# Motordrivare.net
KiCad netlist of a schematic drawn in Altium Designer
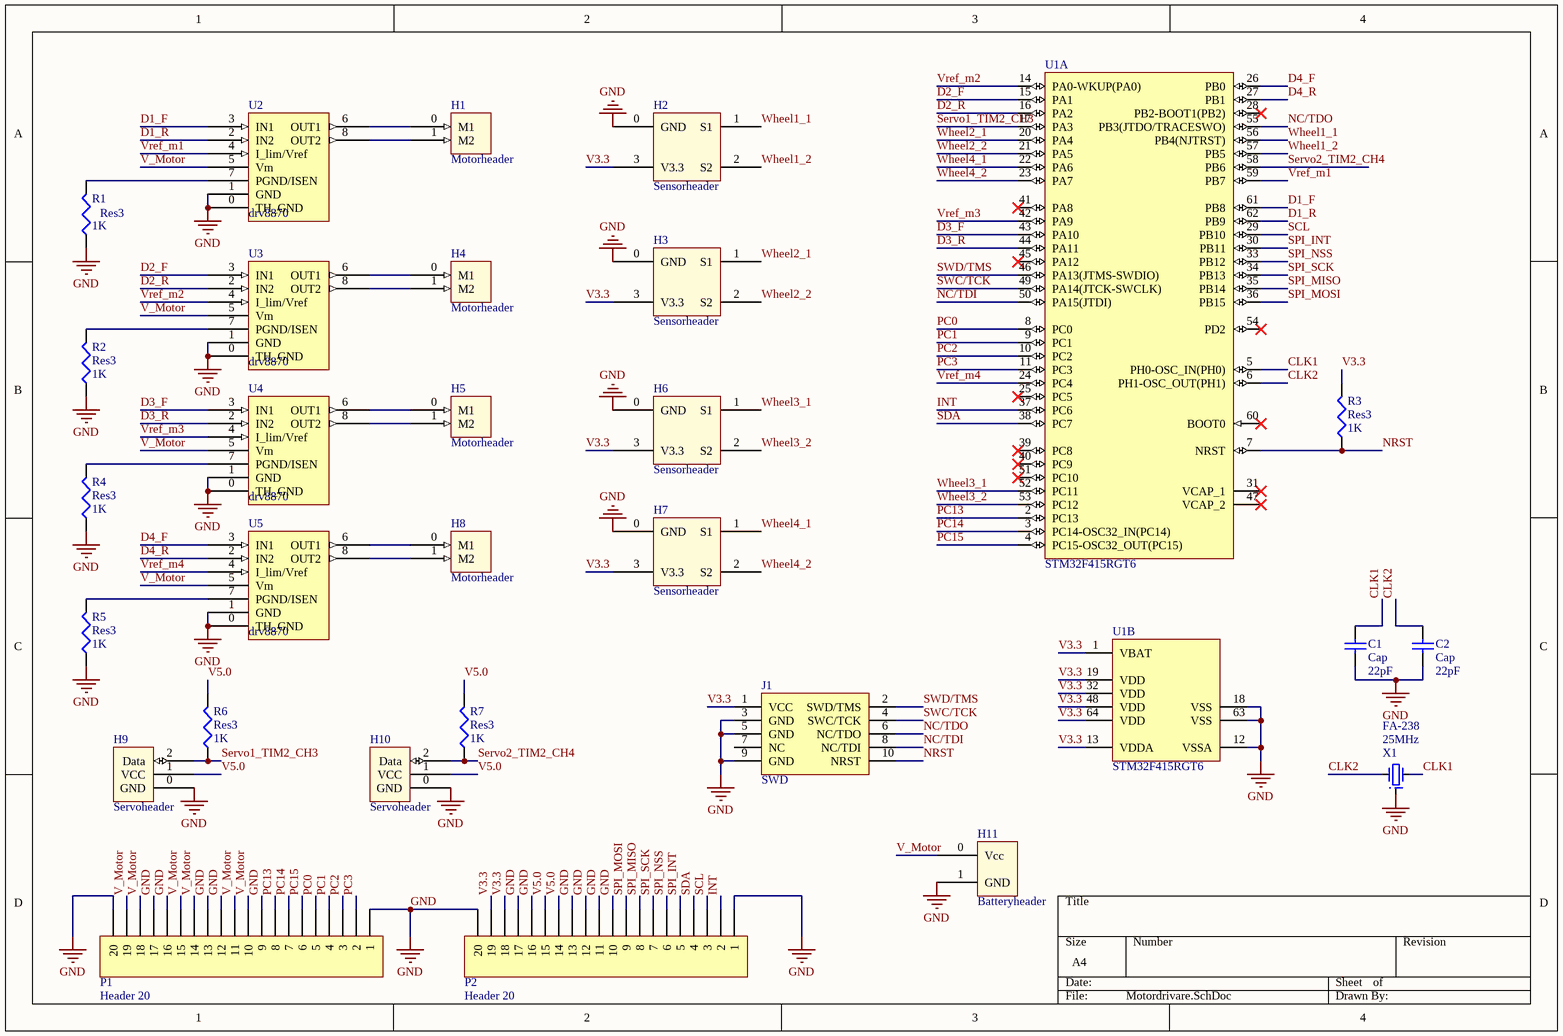
[diagram p0: Motordrivare.SchDoc]

(export (version "E")
  (design (tool "Eeschema 10.0.6"))
  (components
    (comp (ref "C1")
      (value "Cap")
      (footprint "6-0805_M")
      (description "Capacitor")
      (fields (field (name "ALTIUM_VALUE") "22pF") (field (name "PUBLISHER") "Altium Limited"))
      (libsource (lib "Miscellaneous Devices") (part "Cap"))
    )
    (comp (ref "C2")
      (value "Cap")
      (footprint "6-0805_M")
      (description "Capacitor")
      (fields (field (name "ALTIUM_VALUE") "22pF") (field (name "PUBLISHER") "Altium Limited"))
      (libsource (lib "Miscellaneous Devices") (part "Cap"))
    )
    (comp (ref "H1")
      (value "Motorheader")
      (footprint "Motorheader")
      (libsource (lib "Motorheader") (part "Motorheader"))
    )
    (comp (ref "H2")
      (value "Sensorheader")
      (footprint "Sensorheader")
      (libsource (lib "Sensorheader") (part "Sensorheader"))
    )
    (comp (ref "H3")
      (value "Sensorheader")
      (footprint "Sensorheader")
      (libsource (lib "Sensorheader") (part "Sensorheader"))
    )
    (comp (ref "H4")
      (value "Motorheader")
      (footprint "Motorheader")
      (libsource (lib "Motorheader") (part "Motorheader"))
    )
    (comp (ref "H5")
      (value "Motorheader")
      (footprint "Motorheader")
      (libsource (lib "Motorheader") (part "Motorheader"))
    )
    (comp (ref "H6")
      (value "Sensorheader")
      (footprint "Sensorheader")
      (libsource (lib "Sensorheader") (part "Sensorheader"))
    )
    (comp (ref "H7")
      (value "Sensorheader")
      (footprint "Sensorheader")
      (libsource (lib "Sensorheader") (part "Sensorheader"))
    )
    (comp (ref "H8")
      (value "Motorheader")
      (footprint "Motorheader")
      (libsource (lib "Motorheader") (part "Motorheader"))
    )
    (comp (ref "H9")
      (value "Servoheader")
      (footprint "Servoheader")
      (libsource (lib "Servoheader") (part "Servoheader"))
    )
    (comp (ref "H10")
      (value "Servoheader")
      (footprint "Servoheader")
      (libsource (lib "Servoheader") (part "Servoheader"))
    )
    (comp (ref "H11")
      (value "Batteryheader")
      (footprint "Batteryheader")
      (libsource (lib "Batteryheader") (part "Batteryheader"))
    )
    (comp (ref "J1")
      (value "SWD")
      (footprint "hdr_2x5_50mil")
      (description "SWD Header")
      (libsource (lib "lib_connectors") (part "hdr_swd"))
    )
    (comp (ref "P1")
      (value "Header 20")
      (footprint "HDR1X20")
      (description "Header, 20-Pin")
      (fields (field (name "PUBLISHER") "Altium Limited"))
      (libsource (lib "Miscellaneous Connectors") (part "Header 20"))
    )
    (comp (ref "P2")
      (value "Header 20")
      (footprint "HDR1X20")
      (description "Header, 20-Pin")
      (fields (field (name "PUBLISHER") "Altium Limited"))
      (libsource (lib "Miscellaneous Connectors") (part "Header 20"))
    )
    (comp (ref "R1")
      (value "Res3")
      (footprint "J1-0603")
      (description "Resistor")
      (fields (field (name "ALTIUM_VALUE") "1K") (field (name "PUBLISHER") "Altium Limited"))
      (libsource (lib "Miscellaneous Devices") (part "Res3"))
    )
    (comp (ref "R2")
      (value "Res3")
      (footprint "J1-0603")
      (description "Resistor")
      (fields (field (name "ALTIUM_VALUE") "1K") (field (name "PUBLISHER") "Altium Limited"))
      (libsource (lib "Miscellaneous Devices") (part "Res3"))
    )
    (comp (ref "R3")
      (value "Res3")
      (footprint "J1-0603")
      (description "Resistor")
      (fields (field (name "ALTIUM_VALUE") "1K") (field (name "PUBLISHER") "Altium Limited"))
      (libsource (lib "Miscellaneous Devices") (part "Res3"))
    )
    (comp (ref "R4")
      (value "Res3")
      (footprint "J1-0603")
      (description "Resistor")
      (fields (field (name "ALTIUM_VALUE") "1K") (field (name "PUBLISHER") "Altium Limited"))
      (libsource (lib "Miscellaneous Devices") (part "Res3"))
    )
    (comp (ref "R5")
      (value "Res3")
      (footprint "J1-0603")
      (description "Resistor")
      (fields (field (name "ALTIUM_VALUE") "1K") (field (name "PUBLISHER") "Altium Limited"))
      (libsource (lib "Miscellaneous Devices") (part "Res3"))
    )
    (comp (ref "R6")
      (value "Res3")
      (footprint "J1-0603")
      (description "Resistor")
      (fields (field (name "ALTIUM_VALUE") "1K") (field (name "PUBLISHER") "Altium Limited"))
      (libsource (lib "Miscellaneous Devices") (part "Res3"))
    )
    (comp (ref "R7")
      (value "Res3")
      (footprint "J1-0603")
      (description "Resistor")
      (fields (field (name "ALTIUM_VALUE") "1K") (field (name "PUBLISHER") "Altium Limited"))
      (libsource (lib "Miscellaneous Devices") (part "Res3"))
    )
    (comp (ref "U1")
      (value "STM32F415RGT6")
      (footprint "STM-LQFP64_N")
      (fields (field (name "MANUFACTURER") "STMicroelectronics"))
      (libsource (lib "lib_st") (part "STM32F415RGT6"))
    )
    (comp (ref "U2") (value "drv8870") (footprint "DRV8p") (libsource (lib "DRV8870") (part "drv8870")))
    (comp (ref "U3") (value "drv8870") (footprint "DRV8p") (libsource (lib "DRV8870") (part "drv8870")))
    (comp (ref "U4") (value "drv8870") (footprint "DRV8p") (libsource (lib "DRV8870") (part "drv8870")))
    (comp (ref "U5") (value "drv8870") (footprint "DRV8p") (libsource (lib "DRV8870") (part "drv8870")))
    (comp (ref "X1")
      (value "FA-238")
      (footprint "DFN220P320X70-4N")
      (description "Crystal With Shield")
      (fields (field (name "FREQ") "25MHz"))
      (libsource (lib "lib_passives") (part "crystal"))
    )
  )
  (nets
    (net (code "1") (name "/CLK1") (class "Default")
      (node (ref "C1") (pin "2") (pinfunction "2_2") (pintype "passive"))
      (node (ref "U1") (pin "5") (pinfunction "PH0-OSC_IN(PH0)_5") (pintype "bidirectional"))
      (node (ref "X1") (pin "2") (pinfunction "2_2") (pintype "passive"))
    )
    (net (code "2") (name "/CLK2") (class "Default")
      (node (ref "C2") (pin "2") (pinfunction "2_2") (pintype "passive"))
      (node (ref "U1") (pin "6") (pinfunction "PH1-OSC_OUT(PH1)_6") (pintype "bidirectional"))
      (node (ref "X1") (pin "1") (pinfunction "1_1") (pintype "passive"))
    )
    (net (code "3") (name "/D1_F") (class "Default")
      (node (ref "U1") (pin "61") (pinfunction "PB8_61") (pintype "bidirectional"))
      (node (ref "U2") (pin "3") (pinfunction "IN1_3") (pintype "input"))
    )
    (net (code "4") (name "/D1_R") (class "Default")
      (node (ref "U1") (pin "62") (pinfunction "PB9_62") (pintype "bidirectional"))
      (node (ref "U2") (pin "2") (pinfunction "IN2_2") (pintype "input"))
    )
    (net (code "5") (name "/D2_F") (class "Default")
      (node (ref "U1") (pin "15") (pinfunction "PA1_15") (pintype "bidirectional"))
      (node (ref "U3") (pin "3") (pinfunction "IN1_3") (pintype "input"))
    )
    (net (code "6") (name "/D2_R") (class "Default")
      (node (ref "U1") (pin "16") (pinfunction "PA2_16") (pintype "bidirectional"))
      (node (ref "U3") (pin "2") (pinfunction "IN2_2") (pintype "input"))
    )
    (net (code "7") (name "/D3_F") (class "Default")
      (node (ref "U1") (pin "43") (pinfunction "PA10_43") (pintype "bidirectional"))
      (node (ref "U4") (pin "3") (pinfunction "IN1_3") (pintype "input"))
    )
    (net (code "8") (name "/D3_R") (class "Default")
      (node (ref "U1") (pin "44") (pinfunction "PA11_44") (pintype "bidirectional"))
      (node (ref "U4") (pin "2") (pinfunction "IN2_2") (pintype "input"))
    )
    (net (code "9") (name "/D4_F") (class "Default")
      (node (ref "U1") (pin "26") (pinfunction "PB0_26") (pintype "bidirectional"))
      (node (ref "U5") (pin "3") (pinfunction "IN1_3") (pintype "input"))
    )
    (net (code "10") (name "/D4_R") (class "Default")
      (node (ref "U1") (pin "27") (pinfunction "PB1_27") (pintype "bidirectional"))
      (node (ref "U5") (pin "2") (pinfunction "IN2_2") (pintype "input"))
    )
    (net (code "11") (name "/INT") (class "Default")
      (node (ref "P2") (pin "2") (pinfunction "2_2") (pintype "passive"))
      (node (ref "U1") (pin "37") (pinfunction "PC6_37") (pintype "bidirectional"))
    )
    (net (code "12") (name "/NC{slash}TDI") (class "Default")
      (node (ref "J1") (pin "8") (pinfunction "NC/TDI_8") (pintype "passive"))
      (node (ref "U1") (pin "50") (pinfunction "PA15(JTDI)_50") (pintype "bidirectional"))
    )
    (net (code "13") (name "/NC{slash}TDO") (class "Default")
      (node (ref "J1") (pin "6") (pinfunction "NC/TDO_6") (pintype "passive"))
      (node (ref "U1") (pin "55") (pinfunction "PB3(JTDO/TRACESWO)_55") (pintype "bidirectional"))
    )
    (net (code "14") (name "/NRST") (class "Default")
      (node (ref "J1") (pin "10") (pinfunction "NRST_10") (pintype "passive"))
      (node (ref "R3") (pin "1") (pinfunction "1_1") (pintype "passive"))
      (node (ref "U1") (pin "7") (pinfunction "NRST_7") (pintype "bidirectional"))
    )
    (net (code "15") (name "/PC0") (class "Default")
      (node (ref "P1") (pin "5") (pinfunction "5_5") (pintype "passive"))
      (node (ref "U1") (pin "8") (pinfunction "PC0_8") (pintype "bidirectional"))
    )
    (net (code "16") (name "/PC1") (class "Default")
      (node (ref "P1") (pin "4") (pinfunction "4_4") (pintype "passive"))
      (node (ref "U1") (pin "9") (pinfunction "PC1_9") (pintype "bidirectional"))
    )
    (net (code "17") (name "/PC2") (class "Default")
      (node (ref "P1") (pin "3") (pinfunction "3_3") (pintype "passive"))
      (node (ref "U1") (pin "10") (pinfunction "PC2_10") (pintype "bidirectional"))
    )
    (net (code "18") (name "/PC3") (class "Default")
      (node (ref "P1") (pin "2") (pinfunction "2_2") (pintype "passive"))
      (node (ref "U1") (pin "11") (pinfunction "PC3_11") (pintype "bidirectional"))
    )
    (net (code "19") (name "/PC13") (class "Default")
      (node (ref "P1") (pin "8") (pinfunction "8_8") (pintype "passive"))
      (node (ref "U1") (pin "2") (pinfunction "PC13_2") (pintype "bidirectional"))
    )
    (net (code "20") (name "/PC14") (class "Default")
      (node (ref "P1") (pin "7") (pinfunction "7_7") (pintype "passive"))
      (node (ref "U1") (pin "3") (pinfunction "PC14-OSC32_IN(PC14)_3") (pintype "bidirectional"))
    )
    (net (code "21") (name "/PC15") (class "Default")
      (node (ref "P1") (pin "6") (pinfunction "6_6") (pintype "passive"))
      (node (ref "U1") (pin "4") (pinfunction "PC15-OSC32_OUT(PC15)_4") (pintype "bidirectional"))
    )
    (net (code "22") (name "/SCL") (class "Default")
      (node (ref "P2") (pin "3") (pinfunction "3_3") (pintype "passive"))
      (node (ref "U1") (pin "29") (pinfunction "PB10_29") (pintype "bidirectional"))
    )
    (net (code "23") (name "/SDA") (class "Default")
      (node (ref "P2") (pin "4") (pinfunction "4_4") (pintype "passive"))
      (node (ref "U1") (pin "38") (pinfunction "PC7_38") (pintype "bidirectional"))
    )
    (net (code "24") (name "/SPI_INT") (class "Default")
      (node (ref "P2") (pin "5") (pinfunction "5_5") (pintype "passive"))
      (node (ref "U1") (pin "30") (pinfunction "PB11_30") (pintype "bidirectional"))
    )
    (net (code "25") (name "/SPI_MISO") (class "Default")
      (node (ref "P2") (pin "8") (pinfunction "8_8") (pintype "passive"))
      (node (ref "U1") (pin "35") (pinfunction "PB14_35") (pintype "bidirectional"))
    )
    (net (code "26") (name "/SPI_MOSI") (class "Default")
      (node (ref "P2") (pin "9") (pinfunction "9_9") (pintype "passive"))
      (node (ref "U1") (pin "36") (pinfunction "PB15_36") (pintype "bidirectional"))
    )
    (net (code "27") (name "/SPI_NSS") (class "Default")
      (node (ref "P2") (pin "6") (pinfunction "6_6") (pintype "passive"))
      (node (ref "U1") (pin "33") (pinfunction "PB12_33") (pintype "bidirectional"))
    )
    (net (code "28") (name "/SPI_SCK") (class "Default")
      (node (ref "P2") (pin "7") (pinfunction "7_7") (pintype "passive"))
      (node (ref "U1") (pin "34") (pinfunction "PB13_34") (pintype "bidirectional"))
    )
    (net (code "29") (name "/SWC{slash}TCK") (class "Default")
      (node (ref "J1") (pin "4") (pinfunction "SWC/TCK_4") (pintype "passive"))
      (node (ref "U1") (pin "49") (pinfunction "PA14(JTCK-SWCLK)_49") (pintype "bidirectional"))
    )
    (net (code "30") (name "/SWD{slash}TMS") (class "Default")
      (node (ref "J1") (pin "2") (pinfunction "SWD/TMS_2") (pintype "passive"))
      (node (ref "U1") (pin "46") (pinfunction "PA13(JTMS-SWDIO)_46") (pintype "bidirectional"))
    )
    (net (code "31") (name "/Servo1_TIM2_CH3") (class "Default")
      (node (ref "H9") (pin "2") (pinfunction "Data_2") (pintype "bidirectional"))
      (node (ref "R6") (pin "1") (pinfunction "1_1") (pintype "passive"))
      (node (ref "U1") (pin "17") (pinfunction "PA3_17") (pintype "bidirectional"))
    )
    (net (code "32") (name "/Servo2_TIM2_CH4") (class "Default")
      (node (ref "H10") (pin "2") (pinfunction "Data_2") (pintype "bidirectional"))
      (node (ref "R7") (pin "1") (pinfunction "1_1") (pintype "passive"))
      (node (ref "U1") (pin "58") (pinfunction "PB6_58") (pintype "bidirectional"))
    )
    (net (code "33") (name "/V3.3") (class "Default")
      (node (ref "H2") (pin "3") (pinfunction "V3.3_3") (pintype "passive"))
      (node (ref "H3") (pin "3") (pinfunction "V3.3_3") (pintype "passive"))
      (node (ref "H6") (pin "3") (pinfunction "V3.3_3") (pintype "passive"))
      (node (ref "H7") (pin "3") (pinfunction "V3.3_3") (pintype "passive"))
      (node (ref "J1") (pin "1") (pinfunction "VCC_1") (pintype "passive"))
      (node (ref "P2") (pin "18") (pinfunction "18_18") (pintype "passive"))
      (node (ref "P2") (pin "19") (pinfunction "19_19") (pintype "passive"))
      (node (ref "R3") (pin "2") (pinfunction "2_2") (pintype "passive"))
      (node (ref "U1") (pin "1") (pinfunction "VBAT_1") (pintype "power_in"))
      (node (ref "U1") (pin "13") (pinfunction "VDDA_13") (pintype "power_in"))
      (node (ref "U1") (pin "19") (pinfunction "VDD_19") (pintype "power_in"))
      (node (ref "U1") (pin "32") (pinfunction "VDD_32") (pintype "power_in"))
      (node (ref "U1") (pin "48") (pinfunction "VDD_48") (pintype "power_in"))
      (node (ref "U1") (pin "64") (pinfunction "VDD_64") (pintype "power_in"))
    )
    (net (code "34") (name "/V5.0") (class "Default")
      (node (ref "H10") (pin "1") (pinfunction "VCC_1") (pintype "power_in"))
      (node (ref "H9") (pin "1") (pinfunction "VCC_1") (pintype "power_in"))
      (node (ref "P2") (pin "14") (pinfunction "14_14") (pintype "passive"))
      (node (ref "P2") (pin "15") (pinfunction "15_15") (pintype "passive"))
      (node (ref "R6") (pin "2") (pinfunction "2_2") (pintype "passive"))
      (node (ref "R7") (pin "2") (pinfunction "2_2") (pintype "passive"))
    )
    (net (code "35") (name "/V_Motor") (class "Default")
      (node (ref "H11") (pin "0") (pinfunction "Vcc_0") (pintype "power_in"))
      (node (ref "P1") (pin "10") (pinfunction "10_10") (pintype "passive"))
      (node (ref "P1") (pin "11") (pinfunction "11_11") (pintype "passive"))
      (node (ref "P1") (pin "14") (pinfunction "14_14") (pintype "passive"))
      (node (ref "P1") (pin "15") (pinfunction "15_15") (pintype "passive"))
      (node (ref "P1") (pin "18") (pinfunction "18_18") (pintype "passive"))
      (node (ref "P1") (pin "19") (pinfunction "19_19") (pintype "passive"))
      (node (ref "U2") (pin "5") (pinfunction "Vm_5") (pintype "power_in"))
      (node (ref "U3") (pin "5") (pinfunction "Vm_5") (pintype "power_in"))
      (node (ref "U4") (pin "5") (pinfunction "Vm_5") (pintype "power_in"))
      (node (ref "U5") (pin "5") (pinfunction "Vm_5") (pintype "power_in"))
    )
    (net (code "36") (name "/Vref_m1") (class "Default")
      (node (ref "U1") (pin "59") (pinfunction "PB7_59") (pintype "bidirectional"))
      (node (ref "U2") (pin "4") (pinfunction "I_lim/Vref_4") (pintype "input"))
    )
    (net (code "37") (name "/Vref_m2") (class "Default")
      (node (ref "U1") (pin "14") (pinfunction "PA0-WKUP(PA0)_14") (pintype "bidirectional"))
      (node (ref "U3") (pin "4") (pinfunction "I_lim/Vref_4") (pintype "input"))
    )
    (net (code "38") (name "/Vref_m3") (class "Default")
      (node (ref "U1") (pin "42") (pinfunction "PA9_42") (pintype "bidirectional"))
      (node (ref "U4") (pin "4") (pinfunction "I_lim/Vref_4") (pintype "input"))
    )
    (net (code "39") (name "/Vref_m4") (class "Default")
      (node (ref "U1") (pin "24") (pinfunction "PC4_24") (pintype "bidirectional"))
      (node (ref "U5") (pin "4") (pinfunction "I_lim/Vref_4") (pintype "input"))
    )
    (net (code "40") (name "/Wheel1_1") (class "Default")
      (node (ref "H2") (pin "1") (pinfunction "S1_1") (pintype "passive"))
      (node (ref "U1") (pin "56") (pinfunction "PB4(NJTRST)_56") (pintype "bidirectional"))
    )
    (net (code "41") (name "/Wheel1_2") (class "Default")
      (node (ref "H2") (pin "2") (pinfunction "S2_2") (pintype "passive"))
      (node (ref "U1") (pin "57") (pinfunction "PB5_57") (pintype "bidirectional"))
    )
    (net (code "42") (name "/Wheel2_1") (class "Default")
      (node (ref "H3") (pin "1") (pinfunction "S1_1") (pintype "passive"))
      (node (ref "U1") (pin "20") (pinfunction "PA4_20") (pintype "bidirectional"))
    )
    (net (code "43") (name "/Wheel2_2") (class "Default")
      (node (ref "H3") (pin "2") (pinfunction "S2_2") (pintype "passive"))
      (node (ref "U1") (pin "21") (pinfunction "PA5_21") (pintype "bidirectional"))
    )
    (net (code "44") (name "/Wheel3_1") (class "Default")
      (node (ref "H6") (pin "1") (pinfunction "S1_1") (pintype "passive"))
      (node (ref "U1") (pin "52") (pinfunction "PC11_52") (pintype "bidirectional"))
    )
    (net (code "45") (name "/Wheel3_2") (class "Default")
      (node (ref "H6") (pin "2") (pinfunction "S2_2") (pintype "passive"))
      (node (ref "U1") (pin "53") (pinfunction "PC12_53") (pintype "bidirectional"))
    )
    (net (code "46") (name "/Wheel4_1") (class "Default")
      (node (ref "H7") (pin "1") (pinfunction "S1_1") (pintype "passive"))
      (node (ref "U1") (pin "22") (pinfunction "PA6_22") (pintype "bidirectional"))
    )
    (net (code "47") (name "/Wheel4_2") (class "Default")
      (node (ref "H7") (pin "2") (pinfunction "S2_2") (pintype "passive"))
      (node (ref "U1") (pin "23") (pinfunction "PA7_23") (pintype "bidirectional"))
    )
    (net (code "48") (name "GND") (class "Default")
      (node (ref "C1") (pin "1") (pinfunction "1_1") (pintype "passive"))
      (node (ref "C2") (pin "1") (pinfunction "1_1") (pintype "passive"))
      (node (ref "H10") (pin "0") (pinfunction "GND_0") (pintype "power_in"))
      (node (ref "H11") (pin "1") (pinfunction "GND_1") (pintype "power_in"))
      (node (ref "H2") (pin "0") (pinfunction "GND_0") (pintype "power_in"))
      (node (ref "H3") (pin "0") (pinfunction "GND_0") (pintype "power_in"))
      (node (ref "H6") (pin "0") (pinfunction "GND_0") (pintype "power_in"))
      (node (ref "H7") (pin "0") (pinfunction "GND_0") (pintype "power_in"))
      (node (ref "H9") (pin "0") (pinfunction "GND_0") (pintype "power_in"))
      (node (ref "J1") (pin "3") (pinfunction "GND_3") (pintype "passive"))
      (node (ref "J1") (pin "5") (pinfunction "GND_5") (pintype "passive"))
      (node (ref "J1") (pin "9") (pinfunction "GND_9") (pintype "passive"))
      (node (ref "P1") (pin "1") (pinfunction "1_1") (pintype "passive"))
      (node (ref "P1") (pin "12") (pinfunction "12_12") (pintype "passive"))
      (node (ref "P1") (pin "13") (pinfunction "13_13") (pintype "passive"))
      (node (ref "P1") (pin "16") (pinfunction "16_16") (pintype "passive"))
      (node (ref "P1") (pin "17") (pinfunction "17_17") (pintype "passive"))
      (node (ref "P1") (pin "20") (pinfunction "20_20") (pintype "passive"))
      (node (ref "P1") (pin "9") (pinfunction "9_9") (pintype "passive"))
      (node (ref "P2") (pin "1") (pinfunction "1_1") (pintype "passive"))
      (node (ref "P2") (pin "10") (pinfunction "10_10") (pintype "passive"))
      (node (ref "P2") (pin "11") (pinfunction "11_11") (pintype "passive"))
      (node (ref "P2") (pin "12") (pinfunction "12_12") (pintype "passive"))
      (node (ref "P2") (pin "13") (pinfunction "13_13") (pintype "passive"))
      (node (ref "P2") (pin "16") (pinfunction "16_16") (pintype "passive"))
      (node (ref "P2") (pin "17") (pinfunction "17_17") (pintype "passive"))
      (node (ref "P2") (pin "20") (pinfunction "20_20") (pintype "passive"))
      (node (ref "R1") (pin "1") (pinfunction "1_1") (pintype "passive"))
      (node (ref "R2") (pin "1") (pinfunction "1_1") (pintype "passive"))
      (node (ref "R4") (pin "1") (pinfunction "1_1") (pintype "passive"))
      (node (ref "R5") (pin "1") (pinfunction "1_1") (pintype "passive"))
      (node (ref "U1") (pin "12") (pinfunction "VSSA_12") (pintype "power_in"))
      (node (ref "U1") (pin "18") (pinfunction "VSS_18") (pintype "power_in"))
      (node (ref "U1") (pin "63") (pinfunction "VSS_63") (pintype "power_in"))
      (node (ref "U2") (pin "0") (pinfunction "TH_GND_0") (pintype "passive"))
      (node (ref "U2") (pin "1") (pinfunction "GND_1") (pintype "power_in"))
      (node (ref "U3") (pin "0") (pinfunction "TH_GND_0") (pintype "passive"))
      (node (ref "U3") (pin "1") (pinfunction "GND_1") (pintype "power_in"))
      (node (ref "U4") (pin "0") (pinfunction "TH_GND_0") (pintype "passive"))
      (node (ref "U4") (pin "1") (pinfunction "GND_1") (pintype "power_in"))
      (node (ref "U5") (pin "0") (pinfunction "TH_GND_0") (pintype "passive"))
      (node (ref "U5") (pin "1") (pinfunction "GND_1") (pintype "power_in"))
      (node (ref "X1") (pin "SHIELD") (pinfunction "SHIELD_SHIELD") (pintype "passive"))
    )
    (net (code "49") (name "Net-(H1-M1)") (class "Default")
      (node (ref "H1") (pin "0") (pinfunction "M1_0") (pintype "input"))
      (node (ref "U2") (pin "6") (pinfunction "OUT1_6") (pintype "output"))
    )
    (net (code "50") (name "Net-(H1-M2)") (class "Default")
      (node (ref "H1") (pin "1") (pinfunction "M2_1") (pintype "input"))
      (node (ref "U2") (pin "8") (pinfunction "OUT2_8") (pintype "output"))
    )
    (net (code "51") (name "Net-(H4-M1)") (class "Default")
      (node (ref "H4") (pin "0") (pinfunction "M1_0") (pintype "input"))
      (node (ref "U3") (pin "6") (pinfunction "OUT1_6") (pintype "output"))
    )
    (net (code "52") (name "Net-(H4-M2)") (class "Default")
      (node (ref "H4") (pin "1") (pinfunction "M2_1") (pintype "input"))
      (node (ref "U3") (pin "8") (pinfunction "OUT2_8") (pintype "output"))
    )
    (net (code "53") (name "Net-(H5-M1)") (class "Default")
      (node (ref "H5") (pin "0") (pinfunction "M1_0") (pintype "input"))
      (node (ref "U4") (pin "6") (pinfunction "OUT1_6") (pintype "output"))
    )
    (net (code "54") (name "Net-(H5-M2)") (class "Default")
      (node (ref "H5") (pin "1") (pinfunction "M2_1") (pintype "input"))
      (node (ref "U4") (pin "8") (pinfunction "OUT2_8") (pintype "output"))
    )
    (net (code "55") (name "Net-(H8-M1)") (class "Default")
      (node (ref "H8") (pin "0") (pinfunction "M1_0") (pintype "input"))
      (node (ref "U5") (pin "6") (pinfunction "OUT1_6") (pintype "output"))
    )
    (net (code "56") (name "Net-(H8-M2)") (class "Default")
      (node (ref "H8") (pin "1") (pinfunction "M2_1") (pintype "input"))
      (node (ref "U5") (pin "8") (pinfunction "OUT2_8") (pintype "output"))
    )
    (net (code "57") (name "Net-(U2-PGND{slash}ISEN)") (class "Default")
      (node (ref "R1") (pin "2") (pinfunction "2_2") (pintype "passive"))
      (node (ref "U2") (pin "7") (pinfunction "PGND/ISEN_7") (pintype "power_in"))
    )
    (net (code "58") (name "Net-(U3-PGND{slash}ISEN)") (class "Default")
      (node (ref "R2") (pin "2") (pinfunction "2_2") (pintype "passive"))
      (node (ref "U3") (pin "7") (pinfunction "PGND/ISEN_7") (pintype "power_in"))
    )
    (net (code "59") (name "Net-(U4-PGND{slash}ISEN)") (class "Default")
      (node (ref "R4") (pin "2") (pinfunction "2_2") (pintype "passive"))
      (node (ref "U4") (pin "7") (pinfunction "PGND/ISEN_7") (pintype "power_in"))
    )
    (net (code "60") (name "Net-(U5-PGND{slash}ISEN)") (class "Default")
      (node (ref "R5") (pin "2") (pinfunction "2_2") (pintype "passive"))
      (node (ref "U5") (pin "7") (pinfunction "PGND/ISEN_7") (pintype "power_in"))
    )
    (net (code "61") (name "unconnected-(J1-NC-Pad7)") (class "Default")
      (node (ref "J1") (pin "7") (pinfunction "NC_7") (pintype "passive"))
    )
    (net (code "62") (name "unconnected-(U1A-BOOT0-Pad60)") (class "Default")
      (node (ref "U1") (pin "60") (pinfunction "BOOT0_60") (pintype "input+no_connect"))
    )
    (net (code "63") (name "unconnected-(U1A-PA8-Pad41)") (class "Default")
      (node (ref "U1") (pin "41") (pinfunction "PA8_41") (pintype "bidirectional+no_connect"))
    )
    (net (code "64") (name "unconnected-(U1A-PA12-Pad45)") (class "Default")
      (node (ref "U1") (pin "45") (pinfunction "PA12_45") (pintype "bidirectional+no_connect"))
    )
    (net (code "65") (name "unconnected-(U1A-PB2-BOOT1(PB2)-Pad28)") (class "Default")
      (node (ref "U1") (pin "28") (pinfunction "PB2-BOOT1(PB2)_28") (pintype "bidirectional+no_connect"))
    )
    (net (code "66") (name "unconnected-(U1A-PC5-Pad25)") (class "Default")
      (node (ref "U1") (pin "25") (pinfunction "PC5_25") (pintype "bidirectional+no_connect"))
    )
    (net (code "67") (name "unconnected-(U1A-PC8-Pad39)") (class "Default")
      (node (ref "U1") (pin "39") (pinfunction "PC8_39") (pintype "bidirectional+no_connect"))
    )
    (net (code "68") (name "unconnected-(U1A-PC9-Pad40)") (class "Default")
      (node (ref "U1") (pin "40") (pinfunction "PC9_40") (pintype "bidirectional+no_connect"))
    )
    (net (code "69") (name "unconnected-(U1A-PC10-Pad51)") (class "Default")
      (node (ref "U1") (pin "51") (pinfunction "PC10_51") (pintype "bidirectional+no_connect"))
    )
    (net (code "70") (name "unconnected-(U1A-PD2-Pad54)") (class "Default")
      (node (ref "U1") (pin "54") (pinfunction "PD2_54") (pintype "bidirectional+no_connect"))
    )
    (net (code "71") (name "unconnected-(U1A-VCAP_1-Pad31)") (class "Default")
      (node (ref "U1") (pin "31") (pinfunction "VCAP_1_31") (pintype "power_in+no_connect"))
    )
    (net (code "72") (name "unconnected-(U1A-VCAP_2-Pad47)") (class "Default")
      (node (ref "U1") (pin "47") (pinfunction "VCAP_2_47") (pintype "power_in+no_connect"))
    )
  )
)
